# Main.net
KiCad netlist of a schematic drawn in Altium Designer
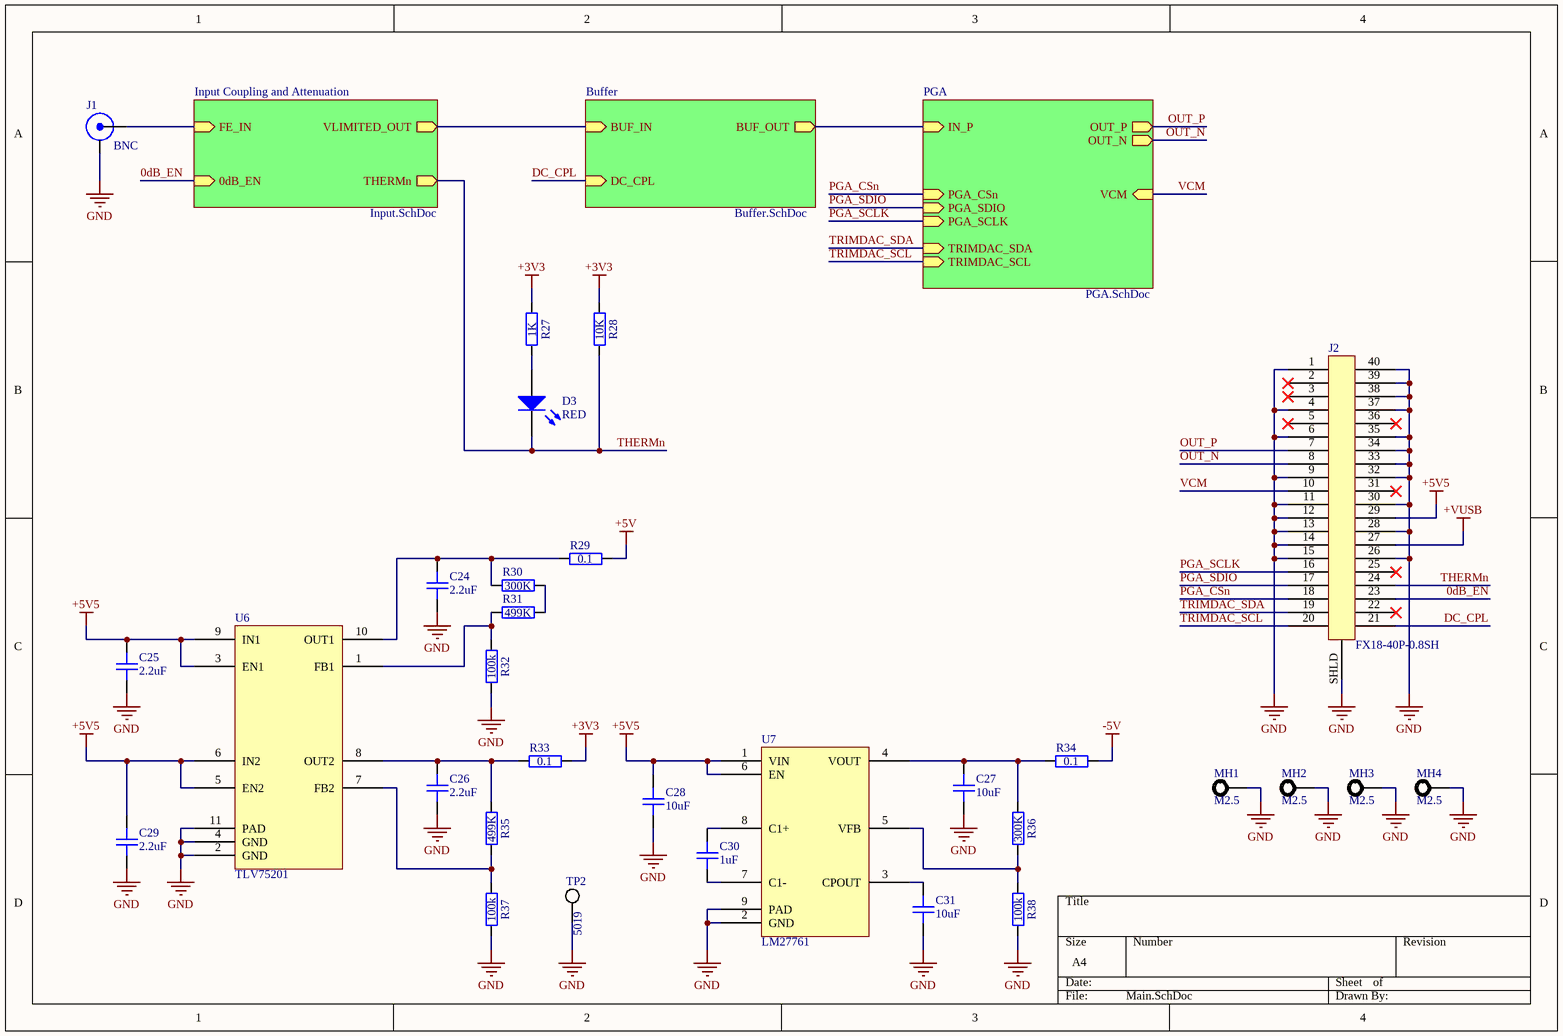
[diagram p0: Main.SchDoc]

(export (version "E")
  (design (tool "Eeschema 10.0.6"))
  (components
    (comp (ref "C24")
      (value "2.2uF")
      (footprint "GEN_C_0402")
      (fields (field (name "Comment") "CAP 2.2uF 10V X5R 0402"))
      (libsource (lib "DSO") (part "CAP 2.2uF 10V X5R 0402"))
    )
    (comp (ref "C25")
      (value "2.2uF")
      (footprint "GEN_C_0402")
      (fields (field (name "Comment") "CAP 2.2uF 10V X5R 0402"))
      (libsource (lib "DSO") (part "CAP 2.2uF 10V X5R 0402"))
    )
    (comp (ref "C26")
      (value "2.2uF")
      (footprint "GEN_C_0402")
      (fields (field (name "Comment") "CAP 2.2uF 10V X5R 0402"))
      (libsource (lib "DSO") (part "CAP 2.2uF 10V X5R 0402"))
    )
    (comp (ref "C27")
      (value "10uF")
      (footprint "GEN_C_0603")
      (fields (field (name "Comment") "CAP 10uF 10V X5R 0603"))
      (libsource (lib "DSO") (part "CAP 10uF 10V X5R 0603"))
    )
    (comp (ref "C28")
      (value "10uF")
      (footprint "GEN_C_0603")
      (fields (field (name "Comment") "CAP 10uF 10V X5R 0603"))
      (libsource (lib "DSO") (part "CAP 10uF 10V X5R 0603"))
    )
    (comp (ref "C29")
      (value "2.2uF")
      (footprint "GEN_C_0402")
      (fields (field (name "Comment") "CAP 2.2uF 10V X5R 0402"))
      (libsource (lib "DSO") (part "CAP 2.2uF 10V X5R 0402"))
    )
    (comp (ref "C30")
      (value "1uF")
      (footprint "GEN_C_0402")
      (fields (field (name "Comment") "CAP 1uF 25V X5R 0402"))
      (libsource (lib "DSO") (part "CAP 1uF 25V X5R 0402"))
    )
    (comp (ref "C31")
      (value "10uF")
      (footprint "GEN_C_0603")
      (fields (field (name "Comment") "CAP 10uF 10V X5R 0603"))
      (libsource (lib "DSO") (part "CAP 10uF 10V X5R 0603"))
    )
    (comp (ref "D3")
      (value "RED")
      (footprint "LED_0603_APT1608")
      (libsource (lib "DSO") (part "LED RED 0603 APT1608"))
    )
    (comp (ref "J1") (value "BNC") (footprint "MOL_0731000105") (libsource (lib "DSO") (part "BNC JACK R/A")))
    (comp (ref "J2")
      (value "FX18-40P-0.8SH")
      (footprint "HIR_FX18-40P-0.8SH")
      (libsource (lib "DSO") (part "CONN HDR FX18-40P-0.8SH"))
    )
    (comp (ref "MH1") (value "M2.5") (footprint "MH M2.5") (libsource (lib "DSO") (part "MH M2.5")))
    (comp (ref "MH2") (value "M2.5") (footprint "MH M2.5") (libsource (lib "DSO") (part "MH M2.5")))
    (comp (ref "MH3") (value "M2.5") (footprint "MH M2.5") (libsource (lib "DSO") (part "MH M2.5")))
    (comp (ref "MH4") (value "M2.5") (footprint "MH M2.5") (libsource (lib "DSO") (part "MH M2.5")))
    (comp (ref "R27")
      (value "1K")
      (footprint "GEN_R_0402")
      (fields (field (name "TOLERANCE") "1%") (field (name "Comment") "RES 1K OHM 1% 1/10W 0402"))
      (libsource (lib "DSO") (part "RES 1K OHM 1% 1/10W 0402"))
    )
    (comp (ref "R28")
      (value "10K")
      (footprint "GEN_R_0402")
      (fields (field (name "TOLERANCE") "1%") (field (name "Comment") "RES 10K OHM 1% 1/10W 0402"))
      (libsource (lib "DSO") (part "RES 10K OHM 1% 1/10W 0402"))
    )
    (comp (ref "R29")
      (value "0.1")
      (footprint "GEN_R_0402")
      (fields (field (name "TOLERANCE") "1%"))
      (libsource (lib "DSO") (part "RES 0.1 OHM 1% 1/6W 0402"))
    )
    (comp (ref "R30")
      (value "300K")
      (footprint "GEN_R_0402")
      (fields (field (name "TOLERANCE") "1%") (field (name "Comment") "RES 300K OHM 1% 1/10W 0402"))
      (libsource (lib "") (part "RES 300K OHM 1% 1/10W 0402_1"))
    )
    (comp (ref "R31")
      (value "499K")
      (footprint "GEN_R_0402")
      (fields (field (name "TOLERANCE") "1%") (field (name "Comment") "RES 499K OHM 1% 1/10W 0402"))
      (libsource (lib "DSO") (part "RES 499K OHM 1% 1/10W 0402"))
    )
    (comp (ref "R32")
      (value "100k")
      (footprint "GEN_R_0402")
      (fields (field (name "TOLERANCE") "1%") (field (name "Comment") "RES 100K OHM 1% 1/10W 0402"))
      (libsource (lib "DSO") (part "RES 100K OHM 1% 1/10W 0402"))
    )
    (comp (ref "R33")
      (value "0.1")
      (footprint "GEN_R_0402")
      (fields (field (name "TOLERANCE") "1%"))
      (libsource (lib "DSO") (part "RES 0.1 OHM 1% 1/6W 0402"))
    )
    (comp (ref "R34")
      (value "0.1")
      (footprint "GEN_R_0402")
      (fields (field (name "TOLERANCE") "1%"))
      (libsource (lib "DSO") (part "RES 0.1 OHM 1% 1/6W 0402"))
    )
    (comp (ref "R35")
      (value "499K")
      (footprint "GEN_R_0402")
      (fields (field (name "TOLERANCE") "1%") (field (name "Comment") "RES 499K OHM 1% 1/10W 0402"))
      (libsource (lib "") (part "RES 499K OHM 1% 1/10W 0402_1"))
    )
    (comp (ref "R36")
      (value "300K")
      (footprint "GEN_R_0402")
      (fields (field (name "TOLERANCE") "1%") (field (name "Comment") "RES 300K OHM 1% 1/10W 0402"))
      (libsource (lib "DSO") (part "RES 300K OHM 1% 1/10W 0402"))
    )
    (comp (ref "R37")
      (value "100k")
      (footprint "GEN_R_0402")
      (fields (field (name "TOLERANCE") "1%") (field (name "Comment") "RES 100K OHM 1% 1/10W 0402"))
      (libsource (lib "DSO") (part "RES 100K OHM 1% 1/10W 0402"))
    )
    (comp (ref "R38")
      (value "100k")
      (footprint "GEN_R_0402")
      (fields (field (name "TOLERANCE") "1%") (field (name "Comment") "RES 100K OHM 1% 1/10W 0402"))
      (libsource (lib "DSO") (part "RES 100K OHM 1% 1/10W 0402"))
    )
    (comp (ref "TP2") (value "5019") (footprint "KEY_5019") (libsource (lib "DSO") (part "TP KEYSTONE 5019")))
    (comp (ref "U6")
      (value "TLV75201")
      (footprint "TI_WSON10_DSQ0010A")
      (libsource (lib "DSO") (part "IC LDO TLV75201"))
    )
    (comp (ref "U7")
      (value "LM27761")
      (footprint "TI_WSON8_DSG0008A")
      (libsource (lib "DSO") (part "IC CPUMP LM27761"))
    )
  )
  (nets
    (net (code "1") (name "+3V3") (class "Default")
      (node (ref "R27") (pin "1") (pinfunction "1_1") (pintype "passive"))
      (node (ref "R28") (pin "2") (pinfunction "2_2") (pintype "passive"))
      (node (ref "R33") (pin "2") (pinfunction "2_2") (pintype "passive"))
    )
    (net (code "2") (name "+5V") (class "Default")
      (node (ref "R29") (pin "2") (pinfunction "2_2") (pintype "passive"))
    )
    (net (code "3") (name "+5V5") (class "Default")
      (node (ref "C25") (pin "2") (pinfunction "2_2") (pintype "passive"))
      (node (ref "C28") (pin "2") (pinfunction "2_2") (pintype "passive"))
      (node (ref "C29") (pin "2") (pinfunction "2_2") (pintype "passive"))
      (node (ref "J2") (pin "29") (pinfunction "29_29") (pintype "passive"))
      (node (ref "U6") (pin "3") (pinfunction "EN1_3") (pintype "passive"))
      (node (ref "U6") (pin "5") (pinfunction "EN2_5") (pintype "passive"))
      (node (ref "U6") (pin "6") (pinfunction "IN2_6") (pintype "power_in"))
      (node (ref "U6") (pin "9") (pinfunction "IN1_9") (pintype "power_in"))
      (node (ref "U7") (pin "1") (pinfunction "VIN_1") (pintype "power_in"))
      (node (ref "U7") (pin "6") (pinfunction "EN_6") (pintype "passive"))
    )
    (net (code "4") (name "+VUSB") (class "Default")
      (node (ref "J2") (pin "27") (pinfunction "27_27") (pintype "passive"))
    )
    (net (code "5") (name "-5V") (class "Default")
      (node (ref "R34") (pin "2") (pinfunction "2_2") (pintype "passive"))
    )
    (net (code "6") (name "/0dB_EN") (class "Default")
      (node (ref "J2") (pin "23") (pinfunction "23_23") (pintype "passive"))
    )
    (net (code "8") (name "/DC_CPL") (class "Default")
      (node (ref "J2") (pin "21") (pinfunction "21_21") (pintype "passive"))
    )
    (net (code "9") (name "/FE_IN") (class "Default")
      (node (ref "J1") (pin "1") (pinfunction "Signal_1") (pintype "passive"))
    )
    (net (code "10") (name "/OUT_N") (class "Default")
      (node (ref "J2") (pin "8") (pinfunction "8_8") (pintype "passive"))
    )
    (net (code "11") (name "/OUT_P") (class "Default")
      (node (ref "J2") (pin "7") (pinfunction "7_7") (pintype "passive"))
    )
    (net (code "12") (name "/PGA_CSn") (class "Default")
      (node (ref "J2") (pin "18") (pinfunction "18_18") (pintype "passive"))
    )
    (net (code "13") (name "/PGA_SCLK") (class "Default")
      (node (ref "J2") (pin "16") (pinfunction "16_16") (pintype "passive"))
    )
    (net (code "14") (name "/PGA_SDIO") (class "Default")
      (node (ref "J2") (pin "17") (pinfunction "17_17") (pintype "passive"))
    )
    (net (code "15") (name "/THERMn") (class "Default")
      (node (ref "D3") (pin "1") (pinfunction "K_1") (pintype "passive"))
      (node (ref "J2") (pin "24") (pinfunction "24_24") (pintype "passive"))
      (node (ref "R28") (pin "1") (pinfunction "1_1") (pintype "passive"))
    )
    (net (code "16") (name "/TRIMDAC_SCL") (class "Default")
      (node (ref "J2") (pin "20") (pinfunction "20_20") (pintype "passive"))
    )
    (net (code "17") (name "/TRIMDAC_SDA") (class "Default")
      (node (ref "J2") (pin "19") (pinfunction "19_19") (pintype "passive"))
    )
    (net (code "18") (name "/VCM") (class "Default")
      (node (ref "J2") (pin "10") (pinfunction "10_10") (pintype "passive"))
    )
    (net (code "20") (name "GND") (class "Default")
      (node (ref "C24") (pin "1") (pinfunction "1_1") (pintype "passive"))
      (node (ref "C25") (pin "1") (pinfunction "1_1") (pintype "passive"))
      (node (ref "C26") (pin "1") (pinfunction "1_1") (pintype "passive"))
      (node (ref "C27") (pin "1") (pinfunction "1_1") (pintype "passive"))
      (node (ref "C28") (pin "1") (pinfunction "1_1") (pintype "passive"))
      (node (ref "C29") (pin "1") (pinfunction "1_1") (pintype "passive"))
      (node (ref "C31") (pin "1") (pinfunction "1_1") (pintype "passive"))
      (node (ref "J1") (pin "2") (pinfunction "SHIELD_2") (pintype "passive"))
      (node (ref "J2") (pin "1") (pinfunction "1_1") (pintype "passive"))
      (node (ref "J2") (pin "11") (pinfunction "11_11") (pintype "passive"))
      (node (ref "J2") (pin "12") (pinfunction "12_12") (pintype "passive"))
      (node (ref "J2") (pin "13") (pinfunction "13_13") (pintype "passive"))
      (node (ref "J2") (pin "14") (pinfunction "14_14") (pintype "passive"))
      (node (ref "J2") (pin "15") (pinfunction "15_15") (pintype "passive"))
      (node (ref "J2") (pin "26") (pinfunction "26_26") (pintype "passive"))
      (node (ref "J2") (pin "28") (pinfunction "28_28") (pintype "passive"))
      (node (ref "J2") (pin "30") (pinfunction "30_30") (pintype "passive"))
      (node (ref "J2") (pin "32") (pinfunction "32_32") (pintype "passive"))
      (node (ref "J2") (pin "33") (pinfunction "33_33") (pintype "passive"))
      (node (ref "J2") (pin "34") (pinfunction "34_34") (pintype "passive"))
      (node (ref "J2") (pin "35") (pinfunction "35_35") (pintype "passive"))
      (node (ref "J2") (pin "37") (pinfunction "37_37") (pintype "passive"))
      (node (ref "J2") (pin "38") (pinfunction "38_38") (pintype "passive"))
      (node (ref "J2") (pin "39") (pinfunction "39_39") (pintype "passive"))
      (node (ref "J2") (pin "4") (pinfunction "4_4") (pintype "passive"))
      (node (ref "J2") (pin "40") (pinfunction "40_40") (pintype "passive"))
      (node (ref "J2") (pin "6") (pinfunction "6_6") (pintype "passive"))
      (node (ref "J2") (pin "9") (pinfunction "9_9") (pintype "passive"))
      (node (ref "J2") (pin "SHLD") (pinfunction "SHLD_SHLD") (pintype "passive"))
      (node (ref "MH1") (pin "1") (pinfunction "1_1") (pintype "passive"))
      (node (ref "MH2") (pin "1") (pinfunction "1_1") (pintype "passive"))
      (node (ref "MH3") (pin "1") (pinfunction "1_1") (pintype "passive"))
      (node (ref "MH4") (pin "1") (pinfunction "1_1") (pintype "passive"))
      (node (ref "R32") (pin "1") (pinfunction "1_1") (pintype "passive"))
      (node (ref "R37") (pin "1") (pinfunction "1_1") (pintype "passive"))
      (node (ref "R38") (pin "1") (pinfunction "1_1") (pintype "passive"))
      (node (ref "TP2") (pin "1") (pinfunction "1_1") (pintype "passive"))
      (node (ref "U6") (pin "11") (pinfunction "PAD_11") (pintype "power_in"))
      (node (ref "U6") (pin "2") (pinfunction "GND_2") (pintype "power_in"))
      (node (ref "U6") (pin "4") (pinfunction "GND_4") (pintype "power_in"))
      (node (ref "U7") (pin "2") (pinfunction "GND_2") (pintype "power_in"))
      (node (ref "U7") (pin "9") (pinfunction "PAD_9") (pintype "power_in"))
    )
    (net (code "21") (name "Net-(D3-A)") (class "Default")
      (node (ref "D3") (pin "2") (pinfunction "A_2") (pintype "passive"))
      (node (ref "R27") (pin "2") (pinfunction "2_2") (pintype "passive"))
    )
    (net (code "22") (name "Net-(R30-Pad1)") (class "Default")
      (node (ref "R30") (pin "1") (pinfunction "1_1") (pintype "passive"))
      (node (ref "R31") (pin "1") (pinfunction "1_1") (pintype "passive"))
    )
    (net (code "23") (name "Net-(U6-FB1)") (class "Default")
      (node (ref "R31") (pin "2") (pinfunction "2_2") (pintype "passive"))
      (node (ref "R32") (pin "2") (pinfunction "2_2") (pintype "passive"))
      (node (ref "U6") (pin "1") (pinfunction "FB1_1") (pintype "passive"))
    )
    (net (code "24") (name "Net-(U6-FB2)") (class "Default")
      (node (ref "R35") (pin "1") (pinfunction "1_1") (pintype "passive"))
      (node (ref "R37") (pin "2") (pinfunction "2_2") (pintype "passive"))
      (node (ref "U6") (pin "7") (pinfunction "FB2_7") (pintype "passive"))
    )
    (net (code "25") (name "Net-(U6-OUT1)") (class "Default")
      (node (ref "C24") (pin "2") (pinfunction "2_2") (pintype "passive"))
      (node (ref "R29") (pin "1") (pinfunction "1_1") (pintype "passive"))
      (node (ref "R30") (pin "2") (pinfunction "2_2") (pintype "passive"))
      (node (ref "U6") (pin "10") (pinfunction "OUT1_10") (pintype "power_in"))
    )
    (net (code "26") (name "Net-(U6-OUT2)") (class "Default")
      (node (ref "C26") (pin "2") (pinfunction "2_2") (pintype "passive"))
      (node (ref "R33") (pin "1") (pinfunction "1_1") (pintype "passive"))
      (node (ref "R35") (pin "2") (pinfunction "2_2") (pintype "passive"))
      (node (ref "U6") (pin "8") (pinfunction "OUT2_8") (pintype "power_in"))
    )
    (net (code "27") (name "Net-(U7-C1+)") (class "Default")
      (node (ref "C30") (pin "2") (pinfunction "2_2") (pintype "passive"))
      (node (ref "U7") (pin "8") (pinfunction "C1+_8") (pintype "passive"))
    )
    (net (code "28") (name "Net-(U7-C1-)") (class "Default")
      (node (ref "C30") (pin "1") (pinfunction "1_1") (pintype "passive"))
      (node (ref "U7") (pin "7") (pinfunction "C1-_7") (pintype "passive"))
    )
    (net (code "29") (name "Net-(U7-CPOUT)") (class "Default")
      (node (ref "C31") (pin "2") (pinfunction "2_2") (pintype "passive"))
      (node (ref "U7") (pin "3") (pinfunction "CPOUT_3") (pintype "passive"))
    )
    (net (code "30") (name "Net-(U7-VFB)") (class "Default")
      (node (ref "R36") (pin "1") (pinfunction "1_1") (pintype "passive"))
      (node (ref "R38") (pin "2") (pinfunction "2_2") (pintype "passive"))
      (node (ref "U7") (pin "5") (pinfunction "VFB_5") (pintype "passive"))
    )
    (net (code "31") (name "Net-(U7-VOUT)") (class "Default")
      (node (ref "C27") (pin "2") (pinfunction "2_2") (pintype "passive"))
      (node (ref "R34") (pin "1") (pinfunction "1_1") (pintype "passive"))
      (node (ref "R36") (pin "2") (pinfunction "2_2") (pintype "passive"))
      (node (ref "U7") (pin "4") (pinfunction "VOUT_4") (pintype "power_in"))
    )
    (net (code "32") (name "unconnected-(J2-Pad2)") (class "Default")
      (node (ref "J2") (pin "2") (pinfunction "2_2") (pintype "passive+no_connect"))
    )
    (net (code "33") (name "unconnected-(J2-Pad3)") (class "Default")
      (node (ref "J2") (pin "3") (pinfunction "3_3") (pintype "passive+no_connect"))
    )
    (net (code "34") (name "unconnected-(J2-Pad5)") (class "Default")
      (node (ref "J2") (pin "5") (pinfunction "5_5") (pintype "passive+no_connect"))
    )
    (net (code "35") (name "unconnected-(J2-Pad22)") (class "Default")
      (node (ref "J2") (pin "22") (pinfunction "22_22") (pintype "passive+no_connect"))
    )
    (net (code "36") (name "unconnected-(J2-Pad25)") (class "Default")
      (node (ref "J2") (pin "25") (pinfunction "25_25") (pintype "passive+no_connect"))
    )
    (net (code "37") (name "unconnected-(J2-Pad31)") (class "Default")
      (node (ref "J2") (pin "31") (pinfunction "31_31") (pintype "passive+no_connect"))
    )
    (net (code "38") (name "unconnected-(J2-Pad36)") (class "Default")
      (node (ref "J2") (pin "36") (pinfunction "36_36") (pintype "passive+no_connect"))
    )
  )
)
